# Channel_Fix.net
KiCad netlist of a schematic drawn in Altium Designer
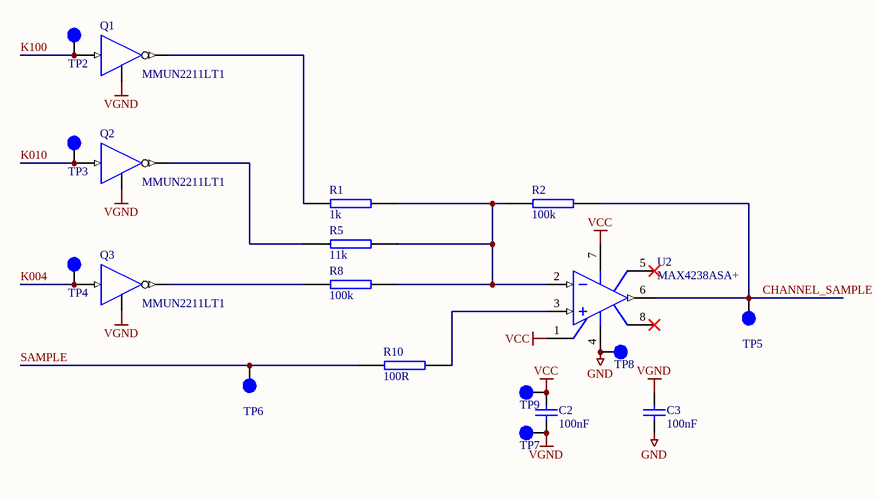
[diagram p0: Channel Fix.SchDoc]

(export (version "E")
  (design (tool "Eeschema 10.0.6"))
  (components
    (comp (ref "C2")
      (value "100nF")
      (footprint "CAP (3D) - 0805")
      (description "Capacitor")
      (libsource (lib "Miscellaneous Devices") (part "Cap"))
    )
    (comp (ref "C3")
      (value "100nF")
      (footprint "CAP (3D) - 0805")
      (description "Capacitor")
      (libsource (lib "Miscellaneous Devices") (part "Cap"))
    )
    (comp (ref "Q1")
      (value "MMUN2211LT1")
      (footprint "SOT23-3L")
      (fields
        (field (name "MOUSER PART NO.") "863-MMUN2211LT1G")
        (field (name "FARNELL PART NO.") "9556648RL")
        (field (name "MANUFACTURER") "ON Semiconductor")
      )
      (libsource (lib "NASCO") (part "MMUN221LT1 NPN DIGITAL TRANSISTOR"))
    )
    (comp (ref "Q2")
      (value "MMUN2211LT1")
      (footprint "SOT23-3L")
      (fields
        (field (name "MOUSER PART NO.") "863-MMUN2211LT1G")
        (field (name "FARNELL PART NO.") "9556648RL")
        (field (name "MANUFACTURER") "ON Semiconductor")
      )
      (libsource (lib "NASCO") (part "MMUN221LT1 NPN DIGITAL TRANSISTOR"))
    )
    (comp (ref "Q3")
      (value "MMUN2211LT1")
      (footprint "SOT23-3L")
      (fields
        (field (name "MOUSER PART NO.") "863-MMUN2211LT1G")
        (field (name "FARNELL PART NO.") "9556648RL")
        (field (name "MANUFACTURER") "ON Semiconductor")
      )
      (libsource (lib "NASCO") (part "MMUN221LT1 NPN DIGITAL TRANSISTOR"))
    )
    (comp (ref "R1")
      (value "1k")
      (footprint "RES (3D) - 0805")
      (description "RESISTOR SMD 0603")
      (libsource (lib "NASCO") (part "RES SMD 0603"))
    )
    (comp (ref "R2")
      (value "100k")
      (footprint "RES (3D) - 0805")
      (description "RESISTOR SMD 0603")
      (libsource (lib "NASCO") (part "RES SMD 0603"))
    )
    (comp (ref "R5")
      (value "11k")
      (footprint "RES (3D) - 0805")
      (description "RESISTOR SMD 0603")
      (libsource (lib "NASCO") (part "RES SMD 0603"))
    )
    (comp (ref "R8")
      (value "100k")
      (footprint "RES (3D) - 0805")
      (description "RESISTOR SMD 0603")
      (libsource (lib "NASCO") (part "RES SMD 0603"))
    )
    (comp (ref "R10")
      (value "100R")
      (footprint "RES (3D) - 0805")
      (description "RESISTOR SMD 0603")
      (libsource (lib "NASCO") (part "RES SMD 0603"))
    )
    (comp (ref "TP2") (value "TestPoint") (footprint "TP") (libsource (lib "NASCO") (part "TestPoint")))
    (comp (ref "TP3") (value "TestPoint") (footprint "TP") (libsource (lib "NASCO") (part "TestPoint")))
    (comp (ref "TP4") (value "TestPoint") (footprint "TP") (libsource (lib "NASCO") (part "TestPoint")))
    (comp (ref "TP5") (value "TestPoint") (footprint "TP") (libsource (lib "NASCO") (part "TestPoint")))
    (comp (ref "TP6") (value "TestPoint") (footprint "TP") (libsource (lib "NASCO") (part "TestPoint")))
    (comp (ref "TP7") (value "TestPoint") (footprint "TP") (libsource (lib "NASCO") (part "TestPoint")))
    (comp (ref "TP8") (value "TestPoint") (footprint "TP") (libsource (lib "NASCO") (part "TestPoint")))
    (comp (ref "TP9") (value "TestPoint") (footprint "TP") (libsource (lib "NASCO") (part "TestPoint")))
    (comp (ref "U2")
      (value "MAX4238ASA+")
      (footprint "SO-8")
      (description "Single Voltage-Feedback Operational Amplifier")
      (fields (field (name "PUBLISHER") "Altium Limited"))
      (libsource (lib "Maxim Operational Amplifier") (part "MAX495CSA"))
    )
  )
  (nets
    (net (code "1") (name "/CHANNEL_SAMPLE") (class "Default")
      (node (ref "R2") (pin "2") (pinfunction "2_2") (pintype "passive"))
      (node (ref "TP5") (pin "1") (pinfunction "1_1") (pintype "passive"))
      (node (ref "U2") (pin "6") (pinfunction "OUT_6") (pintype "output"))
    )
    (net (code "2") (name "/K004") (class "Default")
      (node (ref "Q3") (pin "1") (pinfunction "B_1") (pintype "input"))
      (node (ref "TP4") (pin "1") (pinfunction "1_1") (pintype "passive"))
    )
    (net (code "3") (name "/K010") (class "Default")
      (node (ref "Q2") (pin "1") (pinfunction "B_1") (pintype "input"))
      (node (ref "TP3") (pin "1") (pinfunction "1_1") (pintype "passive"))
    )
    (net (code "4") (name "/K100") (class "Default")
      (node (ref "Q1") (pin "1") (pinfunction "B_1") (pintype "input"))
      (node (ref "TP2") (pin "1") (pinfunction "1_1") (pintype "passive"))
    )
    (net (code "5") (name "/SAMPLE") (class "Default")
      (node (ref "R10") (pin "1") (pinfunction "1_1") (pintype "passive"))
      (node (ref "TP6") (pin "1") (pinfunction "1_1") (pintype "passive"))
    )
    (net (code "6") (name "GND") (class "Default")
      (node (ref "C3") (pin "1") (pinfunction "1_1") (pintype "passive"))
      (node (ref "TP8") (pin "1") (pinfunction "1_1") (pintype "passive"))
      (node (ref "U2") (pin "4") (pinfunction "VEE_4") (pintype "power_in"))
    )
    (net (code "7") (name "Net-(Q1-C)") (class "Default")
      (node (ref "Q1") (pin "3") (pinfunction "C_3") (pintype "output"))
      (node (ref "R1") (pin "1") (pinfunction "1_1") (pintype "passive"))
    )
    (net (code "8") (name "Net-(Q2-C)") (class "Default")
      (node (ref "Q2") (pin "3") (pinfunction "C_3") (pintype "output"))
      (node (ref "R5") (pin "1") (pinfunction "1_1") (pintype "passive"))
    )
    (net (code "9") (name "Net-(Q3-C)") (class "Default")
      (node (ref "Q3") (pin "3") (pinfunction "C_3") (pintype "output"))
      (node (ref "R8") (pin "1") (pinfunction "1_1") (pintype "passive"))
    )
    (net (code "10") (name "Net-(U2-IN+)") (class "Default")
      (node (ref "R10") (pin "2") (pinfunction "2_2") (pintype "passive"))
      (node (ref "U2") (pin "3") (pinfunction "IN+_3") (pintype "input"))
    )
    (net (code "11") (name "Net-(U2-IN-)") (class "Default")
      (node (ref "R1") (pin "2") (pinfunction "2_2") (pintype "passive"))
      (node (ref "R2") (pin "1") (pinfunction "1_1") (pintype "passive"))
      (node (ref "R5") (pin "2") (pinfunction "2_2") (pintype "passive"))
      (node (ref "R8") (pin "2") (pinfunction "2_2") (pintype "passive"))
      (node (ref "U2") (pin "2") (pinfunction "IN-_2") (pintype "input"))
    )
    (net (code "12") (name "VCC") (class "Default")
      (node (ref "C2") (pin "2") (pinfunction "2_2") (pintype "passive"))
      (node (ref "TP9") (pin "1") (pinfunction "1_1") (pintype "passive"))
      (node (ref "U2") (pin "1") (pinfunction "NULL_1") (pintype "passive"))
      (node (ref "U2") (pin "7") (pinfunction "VCC_7") (pintype "power_in"))
    )
    (net (code "13") (name "VGND") (class "Default")
      (node (ref "C2") (pin "1") (pinfunction "1_1") (pintype "passive"))
      (node (ref "C3") (pin "2") (pinfunction "2_2") (pintype "passive"))
      (node (ref "Q1") (pin "2") (pinfunction "E_2") (pintype "passive"))
      (node (ref "Q2") (pin "2") (pinfunction "E_2") (pintype "passive"))
      (node (ref "Q3") (pin "2") (pinfunction "E_2") (pintype "passive"))
      (node (ref "TP7") (pin "1") (pinfunction "1_1") (pintype "passive"))
    )
    (net (code "14") (name "unconnected-(U2-NC-Pad8)") (class "Default")
      (node (ref "U2") (pin "8") (pinfunction "NC_8") (pintype "passive+no_connect"))
    )
    (net (code "15") (name "unconnected-(U2-NULL-Pad5)") (class "Default")
      (node (ref "U2") (pin "5") (pinfunction "NULL_5") (pintype "passive+no_connect"))
    )
  )
)
